# setup.net
KiCad netlist of a schematic drawn in EAGLE
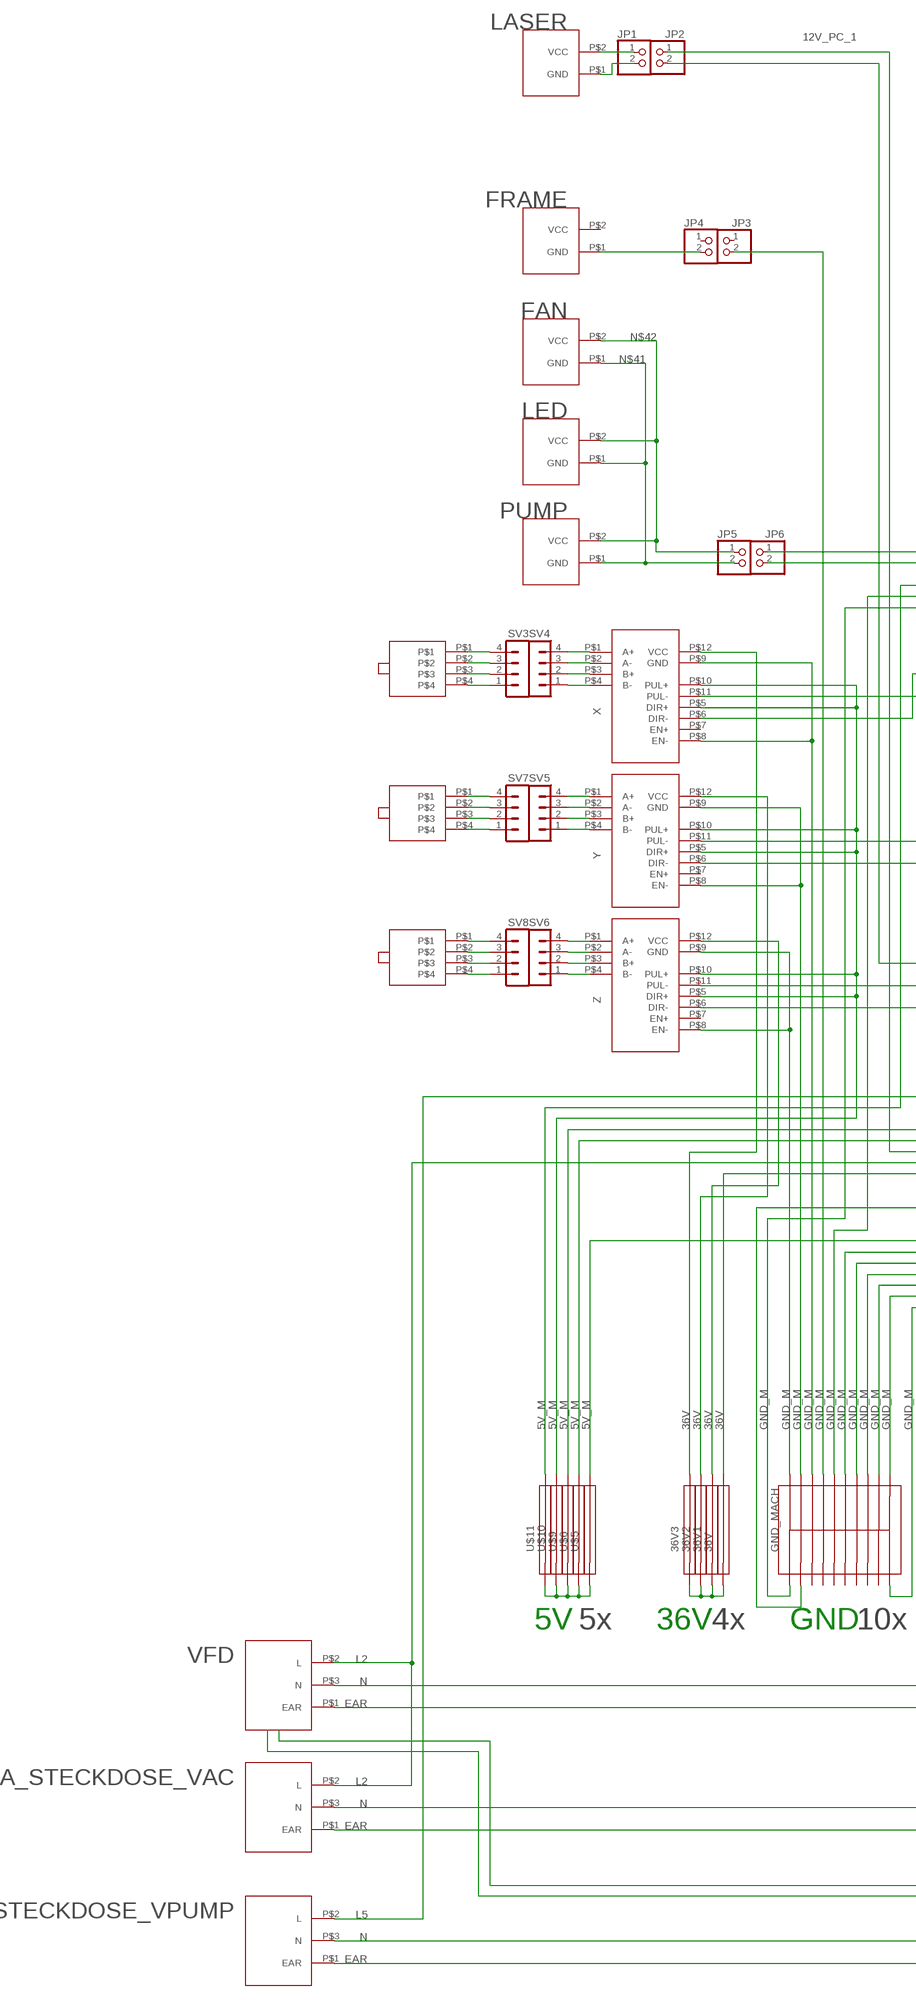
[diagram p0: schematic, sheet 1, part 1 of 3]
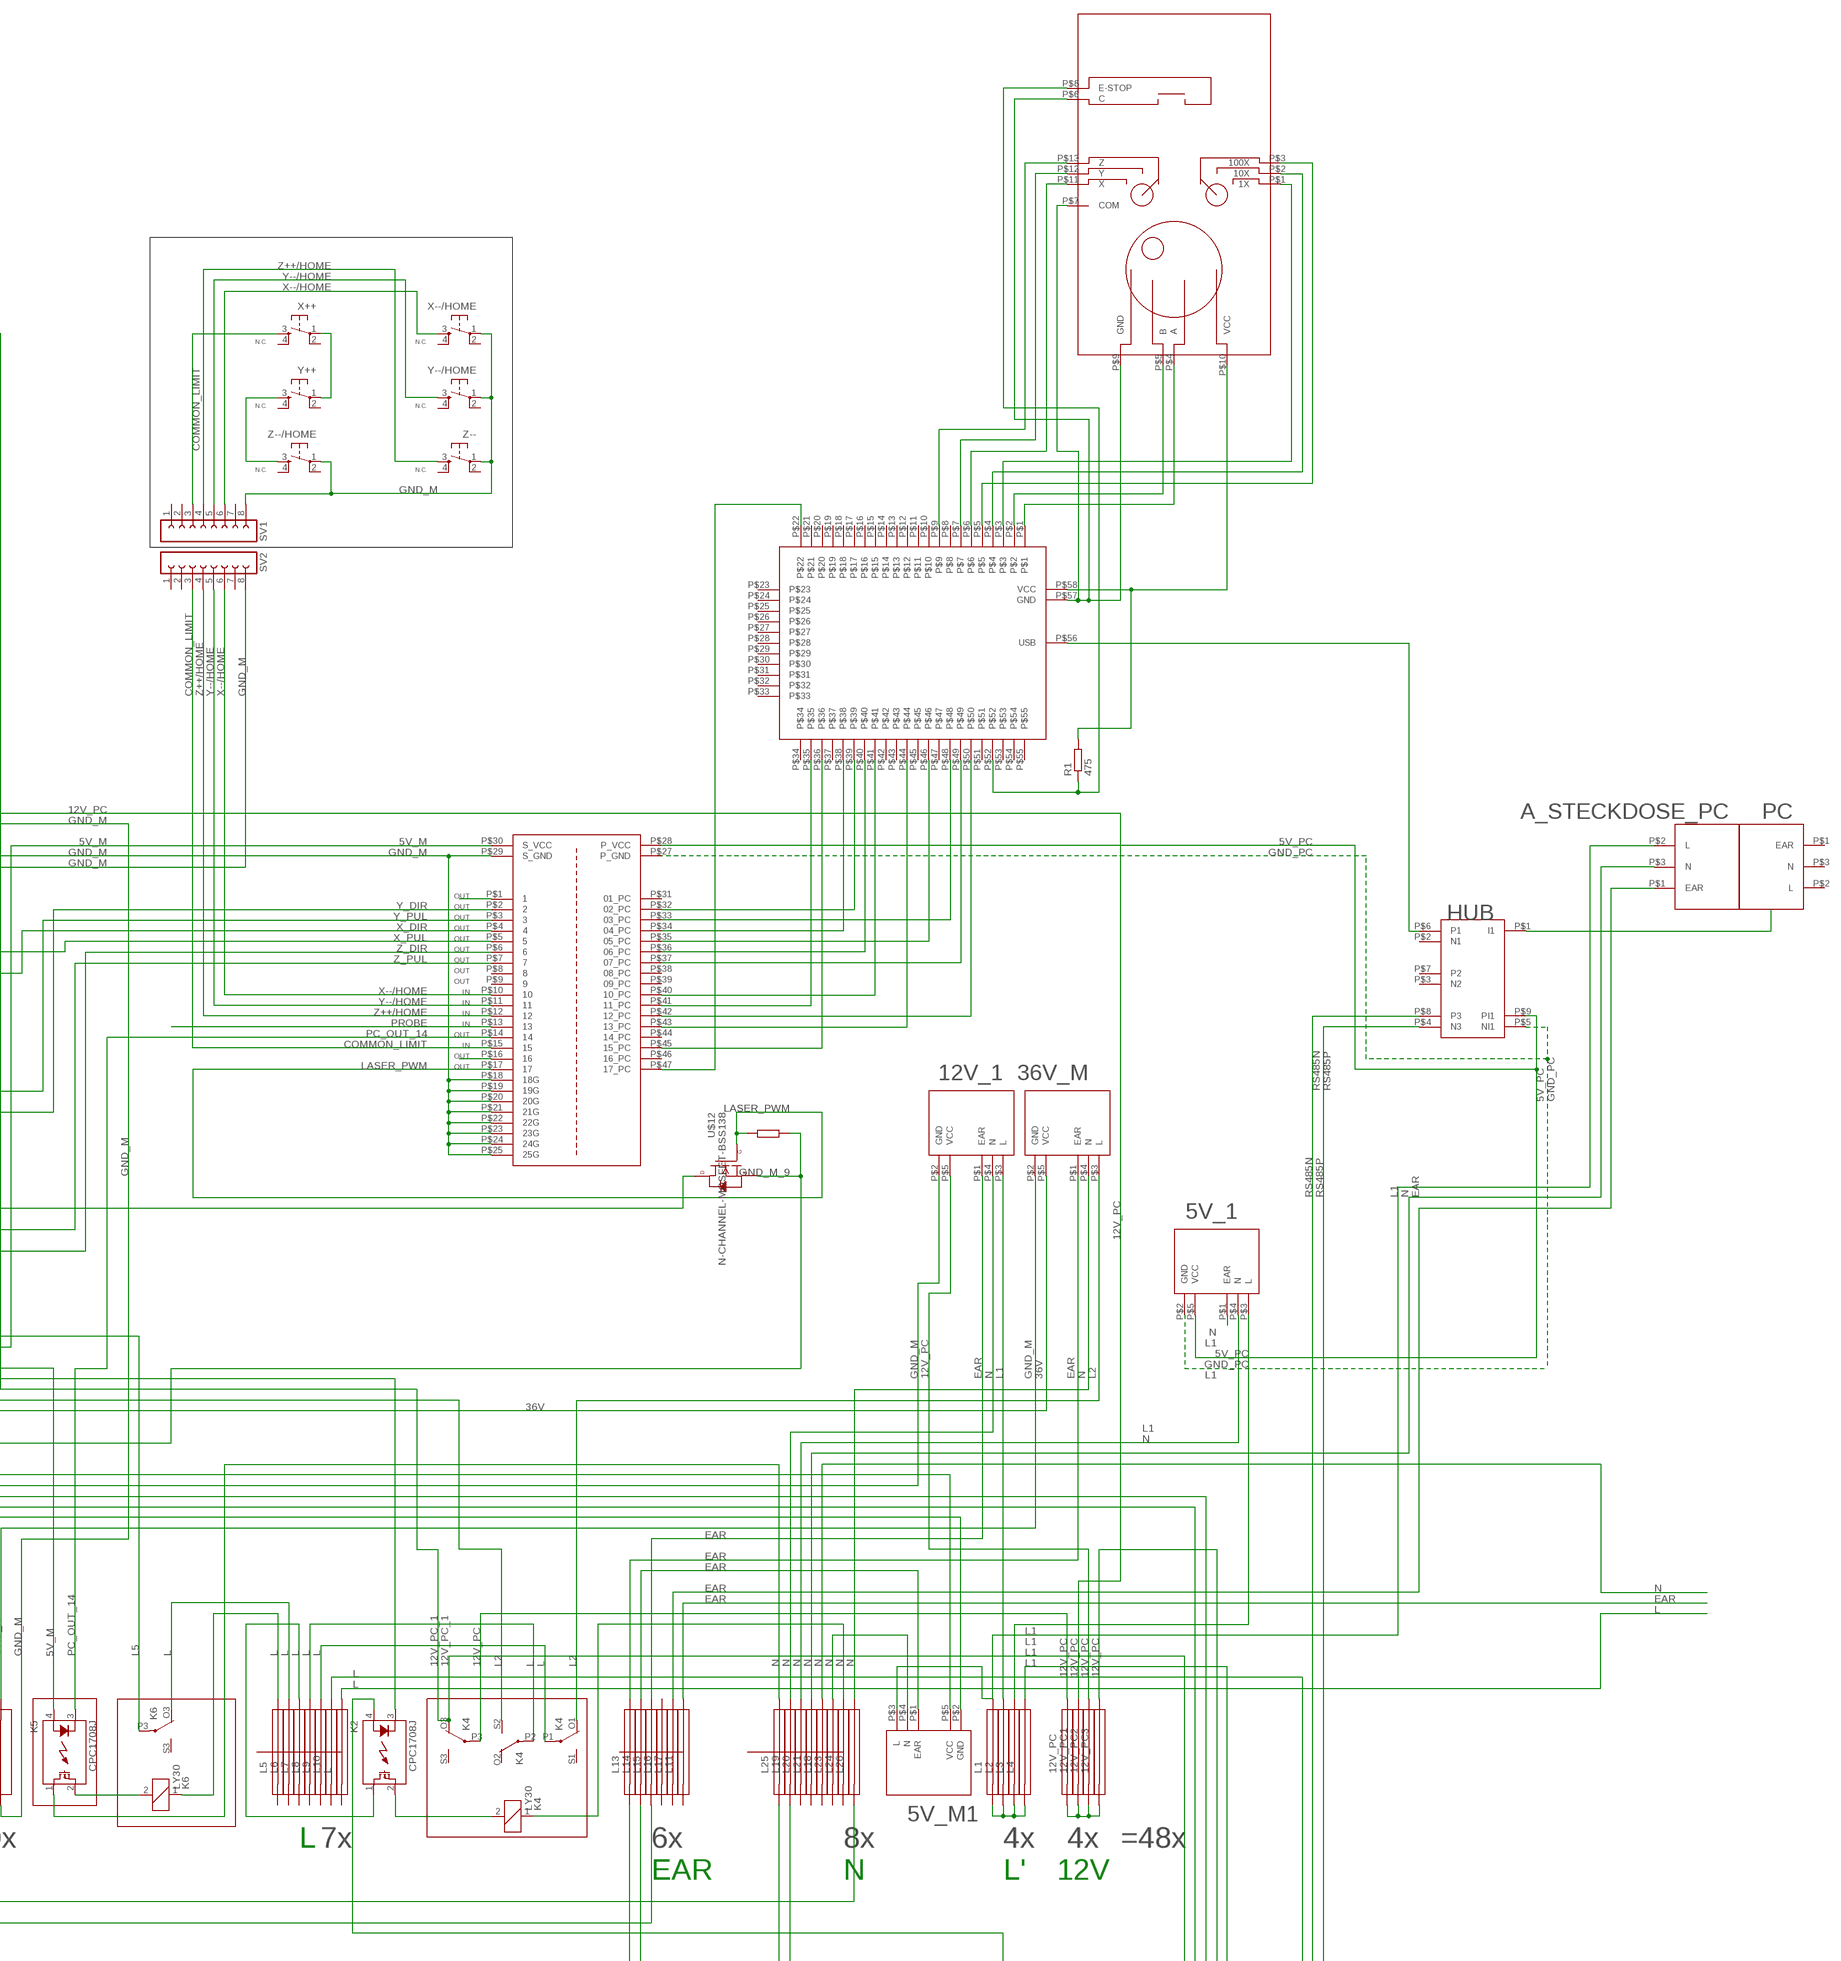
[diagram p1: schematic, sheet 1, part 2 of 3]
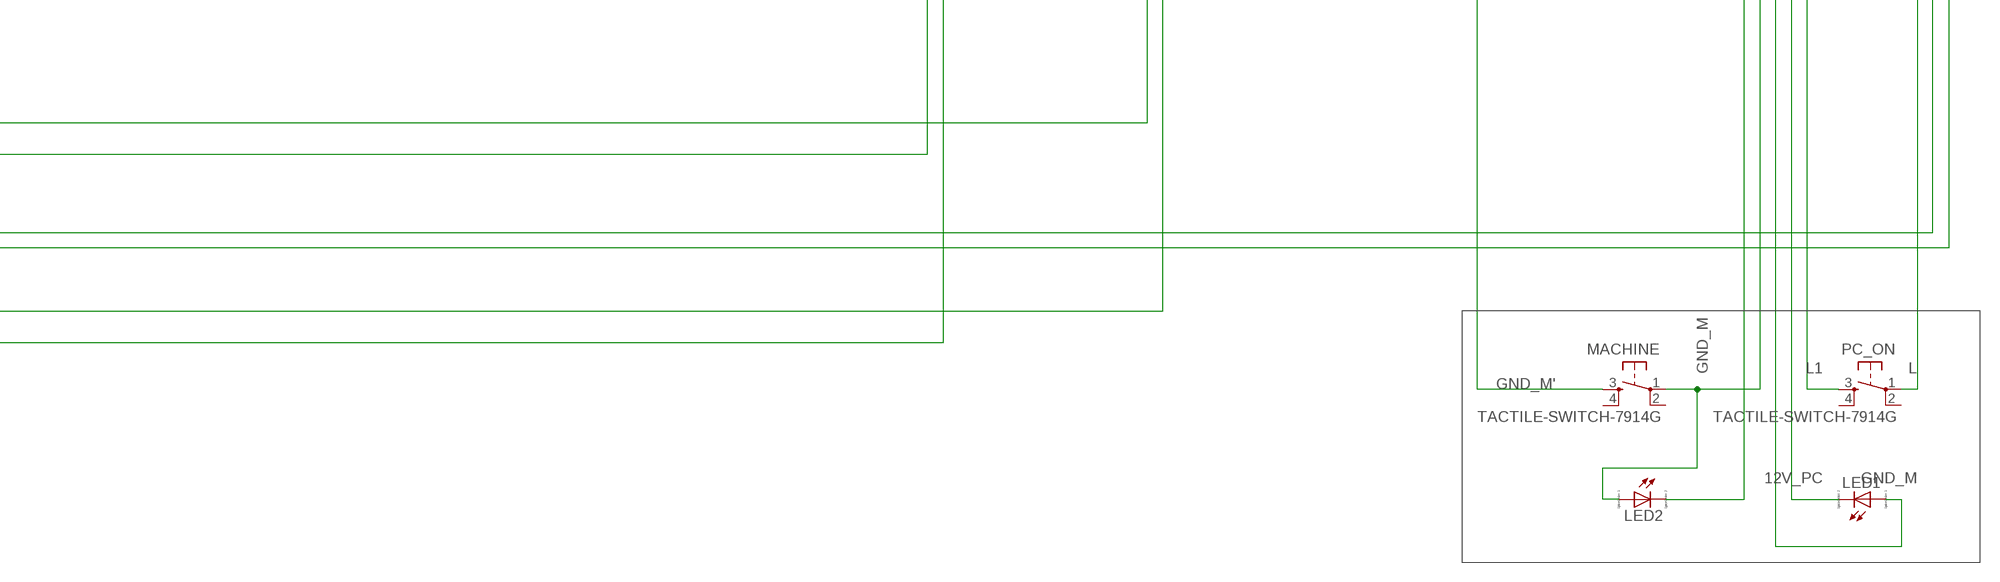
[diagram p2: schematic, sheet 1, part 3 of 3]

(export (version "E")
  (design (tool "Eeschema 10.0.6"))
  (components
    (comp (ref "5V_1")
      (value "PWR")
      (footprint "eagle-import:PWR")
      (libsource (lib "eagle-import") (part "PWR"))
    )
    (comp (ref "5V_M1")
      (value "PWR")
      (footprint "eagle-import:PWR")
      (libsource (lib "eagle-import") (part "PWR"))
    )
    (comp (ref "12V_1")
      (value "PWR")
      (footprint "eagle-import:PWR")
      (libsource (lib "eagle-import") (part "PWR"))
    )
    (comp (ref "12V_PC")
      (value "SINGLE_CONNECTOR")
      (footprint "eagle-import:CONNECTOR")
      (libsource (lib "eagle-import") (part "SINGLE_CONNECTOR"))
    )
    (comp (ref "12V_PC1")
      (value "SINGLE_CONNECTOR")
      (footprint "eagle-import:CONNECTOR")
      (libsource (lib "eagle-import") (part "SINGLE_CONNECTOR"))
    )
    (comp (ref "12V_PC2")
      (value "SINGLE_CONNECTOR")
      (footprint "eagle-import:CONNECTOR")
      (libsource (lib "eagle-import") (part "SINGLE_CONNECTOR"))
    )
    (comp (ref "12V_PC3")
      (value "SINGLE_CONNECTOR")
      (footprint "eagle-import:CONNECTOR")
      (libsource (lib "eagle-import") (part "SINGLE_CONNECTOR"))
    )
    (comp (ref "36V")
      (value "SINGLE_CONNECTOR")
      (footprint "eagle-import:CONNECTOR")
      (libsource (lib "eagle-import") (part "SINGLE_CONNECTOR"))
    )
    (comp (ref "36V1")
      (value "SINGLE_CONNECTOR")
      (footprint "eagle-import:CONNECTOR")
      (libsource (lib "eagle-import") (part "SINGLE_CONNECTOR"))
    )
    (comp (ref "36V2")
      (value "SINGLE_CONNECTOR")
      (footprint "eagle-import:CONNECTOR")
      (libsource (lib "eagle-import") (part "SINGLE_CONNECTOR"))
    )
    (comp (ref "36V3")
      (value "SINGLE_CONNECTOR")
      (footprint "eagle-import:CONNECTOR")
      (libsource (lib "eagle-import") (part "SINGLE_CONNECTOR"))
    )
    (comp (ref "36V_M")
      (value "PWR")
      (footprint "eagle-import:PWR")
      (libsource (lib "eagle-import") (part "PWR"))
    )
    (comp (ref "A_STECKDOSE_PC")
      (value "230VDEV")
      (footprint "eagle-import:230V")
      (libsource (lib "eagle-import") (part "230VDEV"))
    )
    (comp (ref "A_STECKDOSE_VAC")
      (value "230VDEV")
      (footprint "eagle-import:230V")
      (libsource (lib "eagle-import") (part "230VDEV"))
    )
    (comp (ref "A_STECKDOSE_VPUMP")
      (value "230VDEV")
      (footprint "eagle-import:230V")
      (libsource (lib "eagle-import") (part "230VDEV"))
    )
    (comp (ref "FAN")
      (value "LV_DEV")
      (footprint "eagle-import:PUMP")
      (libsource (lib "eagle-import") (part "LV_DEV"))
    )
    (comp (ref "FRAME")
      (value "LV_DEV")
      (footprint "eagle-import:PUMP")
      (libsource (lib "eagle-import") (part "LV_DEV"))
    )
    (comp (ref "GND_MACH")
      (value "CONNECTOR")
      (footprint "eagle-import:CONNECTOR")
      (libsource (lib "eagle-import") (part "CONNECTOR"))
    )
    (comp (ref "JP1")
      (value "PINHD-1X2")
      (footprint "eagle-import:1X02")
      (libsource (lib "eagle-import") (part "PINHD-1X2"))
    )
    (comp (ref "JP2")
      (value "PINHD-1X2")
      (footprint "eagle-import:1X02")
      (libsource (lib "eagle-import") (part "PINHD-1X2"))
    )
    (comp (ref "JP3")
      (value "PINHD-1X2")
      (footprint "eagle-import:1X02")
      (libsource (lib "eagle-import") (part "PINHD-1X2"))
    )
    (comp (ref "JP4")
      (value "PINHD-1X2")
      (footprint "eagle-import:1X02")
      (libsource (lib "eagle-import") (part "PINHD-1X2"))
    )
    (comp (ref "JP5")
      (value "PINHD-1X2")
      (footprint "eagle-import:1X02")
      (libsource (lib "eagle-import") (part "PINHD-1X2"))
    )
    (comp (ref "JP6")
      (value "PINHD-1X2")
      (footprint "eagle-import:1X02")
      (libsource (lib "eagle-import") (part "PINHD-1X2"))
    )
    (comp (ref "K2")
      (value "CPC1708J")
      (footprint "eagle-import:I4-PAC")
      (libsource (lib "eagle-import") (part "CPC1708J"))
    )
    (comp (ref "K4")
      (value "LY30")
      (footprint "eagle-import:LY30")
      (libsource (lib "eagle-import") (part "LY30"))
    )
    (comp (ref "K5")
      (value "CPC1708J")
      (footprint "eagle-import:I4-PAC")
      (libsource (lib "eagle-import") (part "CPC1708J"))
    )
    (comp (ref "K6")
      (value "LY30")
      (footprint "eagle-import:LY30")
      (libsource (lib "eagle-import") (part "LY30"))
    )
    (comp (ref "L")
      (value "SINGLE_CONNECTOR")
      (footprint "eagle-import:CONNECTOR")
      (libsource (lib "eagle-import") (part "SINGLE_CONNECTOR"))
    )
    (comp (ref "L1")
      (value "SINGLE_CONNECTOR")
      (footprint "eagle-import:CONNECTOR")
      (libsource (lib "eagle-import") (part "SINGLE_CONNECTOR"))
    )
    (comp (ref "L2")
      (value "SINGLE_CONNECTOR")
      (footprint "eagle-import:CONNECTOR")
      (libsource (lib "eagle-import") (part "SINGLE_CONNECTOR"))
    )
    (comp (ref "L3")
      (value "SINGLE_CONNECTOR")
      (footprint "eagle-import:CONNECTOR")
      (libsource (lib "eagle-import") (part "SINGLE_CONNECTOR"))
    )
    (comp (ref "L4")
      (value "SINGLE_CONNECTOR")
      (footprint "eagle-import:CONNECTOR")
      (libsource (lib "eagle-import") (part "SINGLE_CONNECTOR"))
    )
    (comp (ref "L5")
      (value "SINGLE_CONNECTOR")
      (footprint "eagle-import:CONNECTOR")
      (libsource (lib "eagle-import") (part "SINGLE_CONNECTOR"))
    )
    (comp (ref "L6")
      (value "SINGLE_CONNECTOR")
      (footprint "eagle-import:CONNECTOR")
      (libsource (lib "eagle-import") (part "SINGLE_CONNECTOR"))
    )
    (comp (ref "L7")
      (value "SINGLE_CONNECTOR")
      (footprint "eagle-import:CONNECTOR")
      (libsource (lib "eagle-import") (part "SINGLE_CONNECTOR"))
    )
    (comp (ref "L8")
      (value "SINGLE_CONNECTOR")
      (footprint "eagle-import:CONNECTOR")
      (libsource (lib "eagle-import") (part "SINGLE_CONNECTOR"))
    )
    (comp (ref "L9")
      (value "SINGLE_CONNECTOR")
      (footprint "eagle-import:CONNECTOR")
      (libsource (lib "eagle-import") (part "SINGLE_CONNECTOR"))
    )
    (comp (ref "L10")
      (value "SINGLE_CONNECTOR")
      (footprint "eagle-import:CONNECTOR")
      (libsource (lib "eagle-import") (part "SINGLE_CONNECTOR"))
    )
    (comp (ref "L11")
      (value "SINGLE_CONNECTOR")
      (footprint "eagle-import:CONNECTOR")
      (libsource (lib "eagle-import") (part "SINGLE_CONNECTOR"))
    )
    (comp (ref "L13")
      (value "SINGLE_CONNECTOR")
      (footprint "eagle-import:CONNECTOR")
      (libsource (lib "eagle-import") (part "SINGLE_CONNECTOR"))
    )
    (comp (ref "L14")
      (value "SINGLE_CONNECTOR")
      (footprint "eagle-import:CONNECTOR")
      (libsource (lib "eagle-import") (part "SINGLE_CONNECTOR"))
    )
    (comp (ref "L15")
      (value "SINGLE_CONNECTOR")
      (footprint "eagle-import:CONNECTOR")
      (libsource (lib "eagle-import") (part "SINGLE_CONNECTOR"))
    )
    (comp (ref "L16")
      (value "SINGLE_CONNECTOR")
      (footprint "eagle-import:CONNECTOR")
      (libsource (lib "eagle-import") (part "SINGLE_CONNECTOR"))
    )
    (comp (ref "L17")
      (value "SINGLE_CONNECTOR")
      (footprint "eagle-import:CONNECTOR")
      (libsource (lib "eagle-import") (part "SINGLE_CONNECTOR"))
    )
    (comp (ref "L18")
      (value "SINGLE_CONNECTOR")
      (footprint "eagle-import:CONNECTOR")
      (libsource (lib "eagle-import") (part "SINGLE_CONNECTOR"))
    )
    (comp (ref "L19")
      (value "SINGLE_CONNECTOR")
      (footprint "eagle-import:CONNECTOR")
      (libsource (lib "eagle-import") (part "SINGLE_CONNECTOR"))
    )
    (comp (ref "L20")
      (value "SINGLE_CONNECTOR")
      (footprint "eagle-import:CONNECTOR")
      (libsource (lib "eagle-import") (part "SINGLE_CONNECTOR"))
    )
    (comp (ref "L21")
      (value "SINGLE_CONNECTOR")
      (footprint "eagle-import:CONNECTOR")
      (libsource (lib "eagle-import") (part "SINGLE_CONNECTOR"))
    )
    (comp (ref "L23")
      (value "SINGLE_CONNECTOR")
      (footprint "eagle-import:CONNECTOR")
      (libsource (lib "eagle-import") (part "SINGLE_CONNECTOR"))
    )
    (comp (ref "L24")
      (value "SINGLE_CONNECTOR")
      (footprint "eagle-import:CONNECTOR")
      (libsource (lib "eagle-import") (part "SINGLE_CONNECTOR"))
    )
    (comp (ref "L25")
      (value "SINGLE_CONNECTOR")
      (footprint "eagle-import:CONNECTOR")
      (libsource (lib "eagle-import") (part "SINGLE_CONNECTOR"))
    )
    (comp (ref "L26")
      (value "SINGLE_CONNECTOR")
      (footprint "eagle-import:CONNECTOR")
      (libsource (lib "eagle-import") (part "SINGLE_CONNECTOR"))
    )
    (comp (ref "LASER")
      (value "LV_DEV")
      (footprint "eagle-import:PUMP")
      (libsource (lib "eagle-import") (part "LV_DEV"))
    )
    (comp (ref "LED")
      (value "LV_DEV")
      (footprint "eagle-import:PUMP")
      (libsource (lib "eagle-import") (part "LV_DEV"))
    )
    (comp (ref "LED1")
      (value "LED_E")
      (footprint "eagle-import:LED_1206")
      (libsource (lib "eagle-import") (part "LED_E"))
    )
    (comp (ref "LED2")
      (value "LED_E")
      (footprint "eagle-import:LED_1206")
      (libsource (lib "eagle-import") (part "LED_E"))
    )
    (comp (ref "MACHINE")
      (value "TACTILE-SWITCH-7914G")
      (footprint "eagle-import:7914G")
      (libsource (lib "eagle-import") (part "TACTILE-SWITCH-7914G"))
    )
    (comp (ref "PC")
      (value "230VDEV")
      (footprint "eagle-import:230V")
      (libsource (lib "eagle-import") (part "230VDEV"))
    )
    (comp (ref "PC_ON")
      (value "TACTILE-SWITCH-7914G")
      (footprint "eagle-import:7914G")
      (libsource (lib "eagle-import") (part "TACTILE-SWITCH-7914G"))
    )
    (comp (ref "PUMP")
      (value "LV_DEV")
      (footprint "eagle-import:PUMP")
      (libsource (lib "eagle-import") (part "LV_DEV"))
    )
    (comp (ref "R1")
      (value "475")
      (footprint "eagle-import:0204V")
      (libsource (lib "eagle-import") (part "R-EU_0204/2V"))
    )
    (comp (ref "SV1")
      (value "FE08-1")
      (footprint "eagle-import:FE08")
      (libsource (lib "eagle-import") (part "FE08-1"))
    )
    (comp (ref "SV2")
      (value "FE08-1")
      (footprint "eagle-import:FE08")
      (libsource (lib "eagle-import") (part "FE08-1"))
    )
    (comp (ref "SV3")
      (value "MA04-1")
      (footprint "eagle-import:MA04-1")
      (libsource (lib "eagle-import") (part "MA04-1"))
    )
    (comp (ref "SV4")
      (value "MA04-1")
      (footprint "eagle-import:MA04-1")
      (libsource (lib "eagle-import") (part "MA04-1"))
    )
    (comp (ref "SV5")
      (value "MA04-1")
      (footprint "eagle-import:MA04-1")
      (libsource (lib "eagle-import") (part "MA04-1"))
    )
    (comp (ref "SV6")
      (value "MA04-1")
      (footprint "eagle-import:MA04-1")
      (libsource (lib "eagle-import") (part "MA04-1"))
    )
    (comp (ref "SV7")
      (value "MA04-1")
      (footprint "eagle-import:MA04-1")
      (libsource (lib "eagle-import") (part "MA04-1"))
    )
    (comp (ref "SV8")
      (value "MA04-1")
      (footprint "eagle-import:MA04-1")
      (libsource (lib "eagle-import") (part "MA04-1"))
    )
    (comp (ref "U$1")
      (value "BOB")
      (footprint "eagle-import:BOB")
      (libsource (lib "eagle-import") (part "BOB"))
    )
    (comp (ref "U$2")
      (value "HUB")
      (footprint "eagle-import:HUB")
      (libsource (lib "eagle-import") (part "HUB"))
    )
    (comp (ref "U$3")
      (value "MOTOR")
      (footprint "eagle-import:MOTOR")
      (libsource (lib "eagle-import") (part "MOTOR"))
    )
    (comp (ref "U$4")
      (value "POKEY57U")
      (footprint "eagle-import:POKEY57U")
      (libsource (lib "eagle-import") (part "POKEY57U"))
    )
    (comp (ref "U$5")
      (value "SINGLE_CONNECTOR")
      (footprint "eagle-import:CONNECTOR")
      (libsource (lib "eagle-import") (part "SINGLE_CONNECTOR"))
    )
    (comp (ref "U$6")
      (value "SINGLE_CONNECTOR")
      (footprint "eagle-import:CONNECTOR")
      (libsource (lib "eagle-import") (part "SINGLE_CONNECTOR"))
    )
    (comp (ref "U$7")
      (value "MOTOR")
      (footprint "eagle-import:MOTOR")
      (libsource (lib "eagle-import") (part "MOTOR"))
    )
    (comp (ref "U$8")
      (value "MOTOR")
      (footprint "eagle-import:MOTOR")
      (libsource (lib "eagle-import") (part "MOTOR"))
    )
    (comp (ref "U$9")
      (value "SINGLE_CONNECTOR")
      (footprint "eagle-import:CONNECTOR")
      (libsource (lib "eagle-import") (part "SINGLE_CONNECTOR"))
    )
    (comp (ref "U$10")
      (value "SINGLE_CONNECTOR")
      (footprint "eagle-import:CONNECTOR")
      (libsource (lib "eagle-import") (part "SINGLE_CONNECTOR"))
    )
    (comp (ref "U$11")
      (value "SINGLE_CONNECTOR")
      (footprint "eagle-import:CONNECTOR")
      (libsource (lib "eagle-import") (part "SINGLE_CONNECTOR"))
    )
    (comp (ref "U$12")
      (value "N-CHANNEL-MOSFET-BSS138")
      (footprint "eagle-import:SOT23-3")
      (libsource (lib "eagle-import") (part "N-CHANNEL-MOSFET-BSS138"))
    )
    (comp (ref "U$13")
      (value "PENDANT")
      (footprint "eagle-import:PENDANT")
      (libsource (lib "eagle-import") (part "PENDANT"))
    )
    (comp (ref "VFD")
      (value "230VDEV")
      (footprint "eagle-import:230V")
      (libsource (lib "eagle-import") (part "230VDEV"))
    )
    (comp (ref "X")
      (value "DRIVER")
      (footprint "eagle-import:DRIVER")
      (libsource (lib "eagle-import") (part "DRIVER"))
    )
    (comp (ref "X++")
      (value "TACTILE-SWITCH-7914G")
      (footprint "eagle-import:7914G")
      (libsource (lib "eagle-import") (part "TACTILE-SWITCH-7914G"))
    )
    (comp (ref "X--/HOME")
      (value "TACTILE-SWITCH-7914G")
      (footprint "eagle-import:7914G")
      (libsource (lib "eagle-import") (part "TACTILE-SWITCH-7914G"))
    )
    (comp (ref "Y")
      (value "DRIVER")
      (footprint "eagle-import:DRIVER")
      (libsource (lib "eagle-import") (part "DRIVER"))
    )
    (comp (ref "Y++")
      (value "TACTILE-SWITCH-7914G")
      (footprint "eagle-import:7914G")
      (libsource (lib "eagle-import") (part "TACTILE-SWITCH-7914G"))
    )
    (comp (ref "Y--/HOME")
      (value "TACTILE-SWITCH-7914G")
      (footprint "eagle-import:7914G")
      (libsource (lib "eagle-import") (part "TACTILE-SWITCH-7914G"))
    )
    (comp (ref "Z")
      (value "DRIVER")
      (footprint "eagle-import:DRIVER")
      (libsource (lib "eagle-import") (part "DRIVER"))
    )
    (comp (ref "Z--")
      (value "TACTILE-SWITCH-7914G")
      (footprint "eagle-import:7914G")
      (libsource (lib "eagle-import") (part "TACTILE-SWITCH-7914G"))
    )
    (comp (ref "Z--/HOME")
      (value "TACTILE-SWITCH-7914G")
      (footprint "eagle-import:7914G")
      (libsource (lib "eagle-import") (part "TACTILE-SWITCH-7914G"))
    )
  )
  (nets
    (net (code "1") (name "/5V_M") (class "Default")
      (node (ref "5V_M1") (pin "P$5") (pinfunction "VCC_P$5") (pintype "bidirectional"))
      (node (ref "K2") (pin "3") (pinfunction "K_3") (pintype "passive"))
      (node (ref "K5") (pin "4") (pinfunction "A_4") (pintype "passive"))
      (node (ref "U$1") (pin "P$30") (pinfunction "S_VCC_P$30") (pintype "bidirectional"))
      (node (ref "U$10") (pin "P$2") (pinfunction "P$11_P$2") (pintype "bidirectional"))
      (node (ref "U$11") (pin "P$2") (pinfunction "P$11_P$2") (pintype "bidirectional"))
      (node (ref "U$5") (pin "P$2") (pinfunction "P$11_P$2") (pintype "bidirectional"))
      (node (ref "U$6") (pin "P$2") (pinfunction "P$11_P$2") (pintype "bidirectional"))
      (node (ref "U$9") (pin "P$2") (pinfunction "P$11_P$2") (pintype "bidirectional"))
      (node (ref "X") (pin "P$10") (pinfunction "PUL+_P$10") (pintype "bidirectional"))
      (node (ref "X") (pin "P$5") (pinfunction "DIR+_P$5") (pintype "bidirectional"))
      (node (ref "Y") (pin "P$10") (pinfunction "PUL+_P$10") (pintype "bidirectional"))
      (node (ref "Y") (pin "P$5") (pinfunction "DIR+_P$5") (pintype "bidirectional"))
      (node (ref "Z") (pin "P$10") (pinfunction "PUL+_P$10") (pintype "bidirectional"))
      (node (ref "Z") (pin "P$5") (pinfunction "DIR+_P$5") (pintype "bidirectional"))
    )
    (net (code "2") (name "/5V_PC") (class "Default")
      (node (ref "5V_1") (pin "P$5") (pinfunction "VCC_P$5") (pintype "bidirectional"))
      (node (ref "U$1") (pin "P$28") (pinfunction "P_VCC_P$28") (pintype "bidirectional"))
      (node (ref "U$2") (pin "P$6") (pinfunction "P1_P$6") (pintype "bidirectional"))
      (node (ref "U$2") (pin "P$9") (pinfunction "PI1_P$9") (pintype "bidirectional"))
      (node (ref "U$4") (pin "P$56") (pinfunction "USB_P$56") (pintype "bidirectional"))
    )
    (net (code "3") (name "/12V_PC") (class "Default")
      (node (ref "12V_1") (pin "P$5") (pinfunction "VCC_P$5") (pintype "bidirectional"))
      (node (ref "12V_PC") (pin "P$2") (pinfunction "P$11_P$2") (pintype "bidirectional"))
      (node (ref "12V_PC1") (pin "P$2") (pinfunction "P$11_P$2") (pintype "bidirectional"))
      (node (ref "12V_PC2") (pin "P$2") (pinfunction "P$11_P$2") (pintype "bidirectional"))
      (node (ref "12V_PC3") (pin "P$2") (pinfunction "P$11_P$2") (pintype "bidirectional"))
      (node (ref "JP6") (pin "1") (pinfunction "1_1") (pintype "passive"))
      (node (ref "K4") (pin "P3") (pinfunction "P_P3") (pintype "passive"))
      (node (ref "LED1") (pin "C") (pinfunction "C_C") (pintype "passive"))
    )
    (net (code "4") (name "/12V_PC_1") (class "Default")
      (node (ref "JP2") (pin "1") (pinfunction "1_1") (pintype "passive"))
      (node (ref "K4") (pin "O3") (pinfunction "O_O3") (pintype "passive"))
      (node (ref "LED2") (pin "C") (pinfunction "C_C") (pintype "passive"))
    )
    (net (code "5") (name "/36V") (class "Default")
      (node (ref "36V") (pin "P$2") (pinfunction "P$11_P$2") (pintype "bidirectional"))
      (node (ref "36V1") (pin "P$2") (pinfunction "P$11_P$2") (pintype "bidirectional"))
      (node (ref "36V2") (pin "P$2") (pinfunction "P$11_P$2") (pintype "bidirectional"))
      (node (ref "36V3") (pin "P$2") (pinfunction "P$11_P$2") (pintype "bidirectional"))
      (node (ref "36V_M") (pin "P$5") (pinfunction "VCC_P$5") (pintype "bidirectional"))
      (node (ref "X") (pin "P$12") (pinfunction "VCC_P$12") (pintype "bidirectional"))
      (node (ref "Y") (pin "P$12") (pinfunction "VCC_P$12") (pintype "bidirectional"))
      (node (ref "Z") (pin "P$12") (pinfunction "VCC_P$12") (pintype "bidirectional"))
    )
    (net (code "6") (name "/COMMON_LIMIT") (class "Default")
      (node (ref "SV1") (pin "3") (pinfunction "3_3") (pintype "passive"))
      (node (ref "SV2") (pin "3") (pinfunction "3_3") (pintype "passive"))
      (node (ref "U$1") (pin "P$15") (pinfunction "15_P$15") (pintype "bidirectional"))
      (node (ref "X++") (pin "3") (pinfunction "3_3") (pintype "passive"))
    )
    (net (code "7") (name "/EAR") (class "Default")
      (node (ref "12V_1") (pin "P$1") (pinfunction "EAR_P$1") (pintype "bidirectional"))
      (node (ref "36V_M") (pin "P$1") (pinfunction "EAR_P$1") (pintype "bidirectional"))
      (node (ref "5V_M1") (pin "P$1") (pinfunction "EAR_P$1") (pintype "bidirectional"))
      (node (ref "A_STECKDOSE_PC") (pin "P$1") (pinfunction "EAR_P$1") (pintype "bidirectional"))
      (node (ref "A_STECKDOSE_VAC") (pin "P$1") (pinfunction "EAR_P$1") (pintype "bidirectional"))
      (node (ref "A_STECKDOSE_VPUMP") (pin "P$1") (pinfunction "EAR_P$1") (pintype "bidirectional"))
      (node (ref "L11") (pin "P$2") (pinfunction "P$11_P$2") (pintype "bidirectional"))
      (node (ref "L13") (pin "P$1") (pinfunction "P$1_P$1") (pintype "bidirectional"))
      (node (ref "L13") (pin "P$2") (pinfunction "P$11_P$2") (pintype "bidirectional"))
      (node (ref "L14") (pin "P$1") (pinfunction "P$1_P$1") (pintype "bidirectional"))
      (node (ref "L14") (pin "P$2") (pinfunction "P$11_P$2") (pintype "bidirectional"))
      (node (ref "L15") (pin "P$1") (pinfunction "P$1_P$1") (pintype "bidirectional"))
      (node (ref "L15") (pin "P$2") (pinfunction "P$11_P$2") (pintype "bidirectional"))
      (node (ref "L17") (pin "P$2") (pinfunction "P$11_P$2") (pintype "bidirectional"))
      (node (ref "VFD") (pin "P$1") (pinfunction "EAR_P$1") (pintype "bidirectional"))
    )
    (net (code "8") (name "/GND_M") (class "Default")
      (node (ref "12V_1") (pin "P$2") (pinfunction "GND_P$2") (pintype "bidirectional"))
      (node (ref "36V_M") (pin "P$2") (pinfunction "GND_P$2") (pintype "bidirectional"))
      (node (ref "5V_M1") (pin "P$2") (pinfunction "GND_P$2") (pintype "bidirectional"))
      (node (ref "GND_MACH") (pin "P$1") (pinfunction "P$1_P$1") (pintype "bidirectional"))
      (node (ref "GND_MACH") (pin "P$10") (pinfunction "P$10_P$10") (pintype "bidirectional"))
      (node (ref "GND_MACH") (pin "P$11") (pinfunction "P$11_P$11") (pintype "bidirectional"))
      (node (ref "GND_MACH") (pin "P$12") (pinfunction "P$12_P$12") (pintype "bidirectional"))
      (node (ref "GND_MACH") (pin "P$13") (pinfunction "P$13_P$13") (pintype "bidirectional"))
      (node (ref "GND_MACH") (pin "P$14") (pinfunction "P$14_P$14") (pintype "bidirectional"))
      (node (ref "GND_MACH") (pin "P$15") (pinfunction "P$15_P$15") (pintype "bidirectional"))
      (node (ref "GND_MACH") (pin "P$16") (pinfunction "P$16_P$16") (pintype "bidirectional"))
      (node (ref "GND_MACH") (pin "P$17") (pinfunction "P$17_P$17") (pintype "bidirectional"))
      (node (ref "GND_MACH") (pin "P$18") (pinfunction "P$18_P$18") (pintype "bidirectional"))
      (node (ref "GND_MACH") (pin "P$19") (pinfunction "P$19_P$19") (pintype "bidirectional"))
      (node (ref "GND_MACH") (pin "P$20") (pinfunction "P$20_P$20") (pintype "bidirectional"))
      (node (ref "JP3") (pin "2") (pinfunction "2_2") (pintype "passive"))
      (node (ref "JP6") (pin "2") (pinfunction "2_2") (pintype "passive"))
      (node (ref "LED1") (pin "A") (pinfunction "A_A") (pintype "passive"))
      (node (ref "LED2") (pin "A") (pinfunction "A_A") (pintype "passive"))
      (node (ref "MACHINE") (pin "1") (pinfunction "1_1") (pintype "passive"))
      (node (ref "SV1") (pin "8") (pinfunction "8_8") (pintype "passive"))
      (node (ref "SV2") (pin "8") (pinfunction "8_8") (pintype "passive"))
      (node (ref "U$1") (pin "P$18") (pinfunction "18G_P$18") (pintype "bidirectional"))
      (node (ref "U$1") (pin "P$19") (pinfunction "19G_P$19") (pintype "bidirectional"))
      (node (ref "U$1") (pin "P$20") (pinfunction "20G_P$20") (pintype "bidirectional"))
      (node (ref "U$1") (pin "P$21") (pinfunction "21G_P$21") (pintype "bidirectional"))
      (node (ref "U$1") (pin "P$22") (pinfunction "22G_P$22") (pintype "bidirectional"))
      (node (ref "U$1") (pin "P$23") (pinfunction "23G_P$23") (pintype "bidirectional"))
      (node (ref "U$1") (pin "P$24") (pinfunction "24G_P$24") (pintype "bidirectional"))
      (node (ref "U$1") (pin "P$25") (pinfunction "25G_P$25") (pintype "bidirectional"))
      (node (ref "U$1") (pin "P$29") (pinfunction "S_GND_P$29") (pintype "bidirectional"))
      (node (ref "X") (pin "P$8") (pinfunction "EN-_P$8") (pintype "bidirectional"))
      (node (ref "X") (pin "P$9") (pinfunction "GND_P$9") (pintype "bidirectional"))
      (node (ref "X--/HOME") (pin "1") (pinfunction "1_1") (pintype "passive"))
      (node (ref "Y") (pin "P$8") (pinfunction "EN-_P$8") (pintype "bidirectional"))
      (node (ref "Y") (pin "P$9") (pinfunction "GND_P$9") (pintype "bidirectional"))
      (node (ref "Y--/HOME") (pin "1") (pinfunction "1_1") (pintype "passive"))
      (node (ref "Z") (pin "P$8") (pinfunction "EN-_P$8") (pintype "bidirectional"))
      (node (ref "Z") (pin "P$9") (pinfunction "GND_P$9") (pintype "bidirectional"))
      (node (ref "Z--") (pin "1") (pinfunction "1_1") (pintype "passive"))
      (node (ref "Z--/HOME") (pin "1") (pinfunction "1_1") (pintype "passive"))
    )
    (net (code "9") (name "/GND_M'") (class "Default")
      (node (ref "K2") (pin "4") (pinfunction "A_4") (pintype "passive"))
      (node (ref "MACHINE") (pin "3") (pinfunction "3_3") (pintype "passive"))
    )
    (net (code "10") (name "/GND_M_9") (class "Default")
      (node (ref "GND_MACH") (pin "P$2") (pinfunction "P$2_P$2") (pintype "bidirectional"))
      (node (ref "U$12") (pin "2") (pinfunction "S_2") (pintype "passive"))
    )
    (net (code "11") (name "/GND_PC") (class "Default")
      (node (ref "5V_1") (pin "P$2") (pinfunction "GND_P$2") (pintype "bidirectional"))
      (node (ref "U$1") (pin "P$27") (pinfunction "P_GND_P$27") (pintype "bidirectional"))
      (node (ref "U$2") (pin "P$5") (pinfunction "NI1_P$5") (pintype "bidirectional"))
    )
    (net (code "12") (name "/L") (class "Default")
      (node (ref "K2") (pin "1") (pinfunction "DS1_1") (pintype "passive"))
      (node (ref "K4") (pin "P1") (pinfunction "P_P1") (pintype "passive"))
      (node (ref "K4") (pin "P2") (pinfunction "P_P2") (pintype "passive"))
      (node (ref "K6") (pin "1") (pinfunction "1_1") (pintype "passive"))
      (node (ref "K6") (pin "O3") (pinfunction "O_O3") (pintype "passive"))
      (node (ref "L") (pin "P$2") (pinfunction "P$11_P$2") (pintype "bidirectional"))
      (node (ref "L10") (pin "P$2") (pinfunction "P$11_P$2") (pintype "bidirectional"))
      (node (ref "L5") (pin "P$2") (pinfunction "P$11_P$2") (pintype "bidirectional"))
      (node (ref "L6") (pin "P$2") (pinfunction "P$11_P$2") (pintype "bidirectional"))
      (node (ref "L7") (pin "P$2") (pinfunction "P$11_P$2") (pintype "bidirectional"))
      (node (ref "L8") (pin "P$2") (pinfunction "P$11_P$2") (pintype "bidirectional"))
      (node (ref "L9") (pin "P$2") (pinfunction "P$11_P$2") (pintype "bidirectional"))
      (node (ref "PC_ON") (pin "1") (pinfunction "1_1") (pintype "passive"))
    )
    (net (code "13") (name "/L1") (class "Default")
      (node (ref "12V_1") (pin "P$3") (pinfunction "L_P$3") (pintype "bidirectional"))
      (node (ref "5V_1") (pin "P$3") (pinfunction "L_P$3") (pintype "bidirectional"))
      (node (ref "5V_M1") (pin "P$3") (pinfunction "L_P$3") (pintype "bidirectional"))
      (node (ref "A_STECKDOSE_PC") (pin "P$2") (pinfunction "L_P$2") (pintype "bidirectional"))
      (node (ref "L1") (pin "P$2") (pinfunction "P$11_P$2") (pintype "bidirectional"))
      (node (ref "L2") (pin "P$2") (pinfunction "P$11_P$2") (pintype "bidirectional"))
      (node (ref "L3") (pin "P$2") (pinfunction "P$11_P$2") (pintype "bidirectional"))
      (node (ref "L4") (pin "P$2") (pinfunction "P$11_P$2") (pintype "bidirectional"))
      (node (ref "PC_ON") (pin "3") (pinfunction "3_3") (pintype "passive"))
    )
    (net (code "14") (name "/L2") (class "Default")
      (node (ref "36V_M") (pin "P$3") (pinfunction "L_P$3") (pintype "bidirectional"))
      (node (ref "A_STECKDOSE_VAC") (pin "P$2") (pinfunction "L_P$2") (pintype "bidirectional"))
      (node (ref "K4") (pin "O1") (pinfunction "O_O1") (pintype "passive"))
      (node (ref "K4") (pin "S2") (pinfunction "S_S2") (pintype "passive"))
      (node (ref "VFD") (pin "P$2") (pinfunction "L_P$2") (pintype "bidirectional"))
    )
    (net (code "15") (name "/L5") (class "Default")
      (node (ref "A_STECKDOSE_VPUMP") (pin "P$2") (pinfunction "L_P$2") (pintype "bidirectional"))
      (node (ref "K6") (pin "P3") (pinfunction "P_P3") (pintype "passive"))
    )
    (net (code "16") (name "/LASER_PWM") (class "Default")
      (node (ref "U$1") (pin "P$17") (pinfunction "17_P$17") (pintype "bidirectional"))
      (node (ref "U$12") (pin "1") (pinfunction "G_1") (pintype "passive"))
    )
    (net (code "17") (name "/N") (class "Default")
      (node (ref "12V_1") (pin "P$4") (pinfunction "N_P$4") (pintype "bidirectional"))
      (node (ref "36V_M") (pin "P$4") (pinfunction "N_P$4") (pintype "bidirectional"))
      (node (ref "5V_1") (pin "P$4") (pinfunction "N_P$4") (pintype "bidirectional"))
      (node (ref "5V_M1") (pin "P$4") (pinfunction "N_P$4") (pintype "bidirectional"))
      (node (ref "A_STECKDOSE_PC") (pin "P$3") (pinfunction "N_P$3") (pintype "bidirectional"))
      (node (ref "A_STECKDOSE_VAC") (pin "P$3") (pinfunction "N_P$3") (pintype "bidirectional"))
      (node (ref "A_STECKDOSE_VPUMP") (pin "P$3") (pinfunction "N_P$3") (pintype "bidirectional"))
      (node (ref "K4") (pin "1") (pinfunction "1_1") (pintype "passive"))
      (node (ref "K5") (pin "1") (pinfunction "DS1_1") (pintype "passive"))
      (node (ref "L18") (pin "P$2") (pinfunction "P$11_P$2") (pintype "bidirectional"))
      (node (ref "L19") (pin "P$1") (pinfunction "P$1_P$1") (pintype "bidirectional"))
      (node (ref "L19") (pin "P$2") (pinfunction "P$11_P$2") (pintype "bidirectional"))
      (node (ref "L20") (pin "P$2") (pinfunction "P$11_P$2") (pintype "bidirectional"))
      (node (ref "L21") (pin "P$2") (pinfunction "P$11_P$2") (pintype "bidirectional"))
      (node (ref "L23") (pin "P$2") (pinfunction "P$11_P$2") (pintype "bidirectional"))
      (node (ref "L24") (pin "P$2") (pinfunction "P$11_P$2") (pintype "bidirectional"))
      (node (ref "L25") (pin "P$1") (pinfunction "P$1_P$1") (pintype "bidirectional"))
      (node (ref "L25") (pin "P$2") (pinfunction "P$11_P$2") (pintype "bidirectional"))
      (node (ref "L26") (pin "P$1") (pinfunction "P$1_P$1") (pintype "bidirectional"))
      (node (ref "L26") (pin "P$2") (pinfunction "P$11_P$2") (pintype "bidirectional"))
      (node (ref "VFD") (pin "P$3") (pinfunction "N_P$3") (pintype "bidirectional"))
    )
    (net (code "18") (name "/N$41") (class "Default")
      (node (ref "FAN") (pin "P$1") (pinfunction "GND_P$1") (pintype "bidirectional"))
      (node (ref "JP5") (pin "2") (pinfunction "2_2") (pintype "passive"))
      (node (ref "LED") (pin "P$1") (pinfunction "GND_P$1") (pintype "bidirectional"))
      (node (ref "PUMP") (pin "P$1") (pinfunction "GND_P$1") (pintype "bidirectional"))
    )
    (net (code "19") (name "/N$42") (class "Default")
      (node (ref "FAN") (pin "P$2") (pinfunction "VCC_P$2") (pintype "bidirectional"))
      (node (ref "JP5") (pin "1") (pinfunction "1_1") (pintype "passive"))
      (node (ref "LED") (pin "P$2") (pinfunction "VCC_P$2") (pintype "bidirectional"))
      (node (ref "PUMP") (pin "P$2") (pinfunction "VCC_P$2") (pintype "bidirectional"))
    )
    (net (code "20") (name "/PC_OUT_14") (class "Default")
      (node (ref "K5") (pin "3") (pinfunction "K_3") (pintype "passive"))
      (node (ref "U$1") (pin "P$14") (pinfunction "14_P$14") (pintype "bidirectional"))
    )
    (net (code "21") (name "/PROBE") (class "Default")
      (node (ref "U$1") (pin "P$13") (pinfunction "13_P$13") (pintype "bidirectional"))
    )
    (net (code "22") (name "/RS485N") (class "Default")
      (node (ref "U$2") (pin "P$8") (pinfunction "P3_P$8") (pintype "bidirectional"))
    )
    (net (code "23") (name "/RS485P") (class "Default")
      (node (ref "U$2") (pin "P$4") (pinfunction "N3_P$4") (pintype "bidirectional"))
    )
    (net (code "24") (name "/X--{slash}HOME") (class "Default")
      (node (ref "SV1") (pin "6") (pinfunction "6_6") (pintype "passive"))
      (node (ref "SV2") (pin "6") (pinfunction "6_6") (pintype "passive"))
      (node (ref "U$1") (pin "P$10") (pinfunction "10_P$10") (pintype "bidirectional"))
      (node (ref "X--/HOME") (pin "3") (pinfunction "3_3") (pintype "passive"))
    )
    (net (code "25") (name "/X_DIR") (class "Default")
      (node (ref "U$1") (pin "P$4") (pinfunction "4_P$4") (pintype "bidirectional"))
      (node (ref "X") (pin "P$6") (pinfunction "DIR-_P$6") (pintype "bidirectional"))
    )
    (net (code "26") (name "/X_PUL") (class "Default")
      (node (ref "U$1") (pin "P$5") (pinfunction "5_P$5") (pintype "bidirectional"))
      (node (ref "X") (pin "P$11") (pinfunction "PUL-_P$11") (pintype "bidirectional"))
    )
    (net (code "27") (name "/Y--{slash}HOME") (class "Default")
      (node (ref "SV1") (pin "5") (pinfunction "5_5") (pintype "passive"))
      (node (ref "SV2") (pin "5") (pinfunction "5_5") (pintype "passive"))
      (node (ref "U$1") (pin "P$11") (pinfunction "11_P$11") (pintype "bidirectional"))
      (node (ref "Y--/HOME") (pin "3") (pinfunction "3_3") (pintype "passive"))
    )
    (net (code "28") (name "/Y_DIR") (class "Default")
      (node (ref "U$1") (pin "P$2") (pinfunction "2_P$2") (pintype "bidirectional"))
      (node (ref "Y") (pin "P$6") (pinfunction "DIR-_P$6") (pintype "bidirectional"))
    )
    (net (code "29") (name "/Y_PUL") (class "Default")
      (node (ref "U$1") (pin "P$3") (pinfunction "3_P$3") (pintype "bidirectional"))
      (node (ref "Y") (pin "P$11") (pinfunction "PUL-_P$11") (pintype "bidirectional"))
    )
    (net (code "30") (name "/Z++{slash}HOME") (class "Default")
      (node (ref "SV1") (pin "4") (pinfunction "4_4") (pintype "passive"))
      (node (ref "SV2") (pin "4") (pinfunction "4_4") (pintype "passive"))
      (node (ref "U$1") (pin "P$12") (pinfunction "12_P$12") (pintype "bidirectional"))
      (node (ref "Z--") (pin "3") (pinfunction "3_3") (pintype "passive"))
    )
    (net (code "31") (name "/Z_DIR") (class "Default")
      (node (ref "U$1") (pin "P$6") (pinfunction "6_P$6") (pintype "bidirectional"))
      (node (ref "Z") (pin "P$6") (pinfunction "DIR-_P$6") (pintype "bidirectional"))
    )
    (net (code "32") (name "/Z_PUL") (class "Default")
      (node (ref "U$1") (pin "P$7") (pinfunction "7_P$7") (pintype "bidirectional"))
      (node (ref "Z") (pin "P$11") (pinfunction "PUL-_P$11") (pintype "bidirectional"))
    )
    (net (code "33") (name "Net-(12V_PC-PadP$1)") (class "Default")
      (node (ref "12V_PC") (pin "P$1") (pinfunction "P$1_P$1") (pintype "bidirectional"))
      (node (ref "12V_PC1") (pin "P$1") (pinfunction "P$1_P$1") (pintype "bidirectional"))
      (node (ref "12V_PC2") (pin "P$1") (pinfunction "P$1_P$1") (pintype "bidirectional"))
      (node (ref "12V_PC3") (pin "P$1") (pinfunction "P$1_P$1") (pintype "bidirectional"))
    )
    (net (code "34") (name "Net-(36V-PadP$1)") (class "Default")
      (node (ref "36V") (pin "P$1") (pinfunction "P$1_P$1") (pintype "bidirectional"))
      (node (ref "36V1") (pin "P$1") (pinfunction "P$1_P$1") (pintype "bidirectional"))
      (node (ref "36V2") (pin "P$1") (pinfunction "P$1_P$1") (pintype "bidirectional"))
      (node (ref "36V3") (pin "P$1") (pinfunction "P$1_P$1") (pintype "bidirectional"))
    )
    (net (code "35") (name "Net-(FRAME-GND)") (class "Default")
      (node (ref "FRAME") (pin "P$1") (pinfunction "GND_P$1") (pintype "bidirectional"))
      (node (ref "JP4") (pin "2") (pinfunction "2_2") (pintype "passive"))
    )
    (net (code "36") (name "Net-(K2-DS2)") (class "Default")
      (node (ref "K2") (pin "2") (pinfunction "DS2_2") (pintype "passive"))
      (node (ref "K4") (pin "2") (pinfunction "2_2") (pintype "passive"))
    )
    (net (code "37") (name "Net-(K5-DS2)") (class "Default")
      (node (ref "K5") (pin "2") (pinfunction "DS2_2") (pintype "passive"))
      (node (ref "K6") (pin "2") (pinfunction "2_2") (pintype "passive"))
    )
    (net (code "38") (name "Net-(L1-PadP$1)") (class "Default")
      (node (ref "L1") (pin "P$1") (pinfunction "P$1_P$1") (pintype "bidirectional"))
      (node (ref "L2") (pin "P$1") (pinfunction "P$1_P$1") (pintype "bidirectional"))
      (node (ref "L3") (pin "P$1") (pinfunction "P$1_P$1") (pintype "bidirectional"))
      (node (ref "L4") (pin "P$1") (pinfunction "P$1_P$1") (pintype "bidirectional"))
    )
    (net (code "39") (name "Net-(LASER-GND)") (class "Default")
      (node (ref "JP1") (pin "2") (pinfunction "2_2") (pintype "passive"))
      (node (ref "LASER") (pin "P$1") (pinfunction "GND_P$1") (pintype "bidirectional"))
    )
    (net (code "40") (name "Net-(LASER-VCC)") (class "Default")
      (node (ref "JP1") (pin "1") (pinfunction "1_1") (pintype "passive"))
      (node (ref "LASER") (pin "P$2") (pinfunction "VCC_P$2") (pintype "bidirectional"))
    )
    (net (code "41") (name "Net-(SV3-Pad1)") (class "Default")
      (node (ref "SV3") (pin "1") (pinfunction "1_1") (pintype "passive"))
      (node (ref "U$3") (pin "P$4") (pinfunction "P$4_P$4") (pintype "bidirectional"))
    )
    (net (code "42") (name "Net-(SV3-Pad2)") (class "Default")
      (node (ref "SV3") (pin "2") (pinfunction "2_2") (pintype "passive"))
      (node (ref "U$3") (pin "P$3") (pinfunction "P$3_P$3") (pintype "bidirectional"))
    )
    (net (code "43") (name "Net-(SV3-Pad3)") (class "Default")
      (node (ref "SV3") (pin "3") (pinfunction "3_3") (pintype "passive"))
      (node (ref "U$3") (pin "P$2") (pinfunction "P$2_P$2") (pintype "bidirectional"))
    )
    (net (code "44") (name "Net-(SV3-Pad4)") (class "Default")
      (node (ref "SV3") (pin "4") (pinfunction "4_4") (pintype "passive"))
      (node (ref "U$3") (pin "P$1") (pinfunction "P$1_P$1") (pintype "bidirectional"))
    )
    (net (code "45") (name "Net-(SV7-Pad1)") (class "Default")
      (node (ref "SV7") (pin "1") (pinfunction "1_1") (pintype "passive"))
      (node (ref "U$7") (pin "P$4") (pinfunction "P$4_P$4") (pintype "bidirectional"))
    )
    (net (code "46") (name "Net-(SV7-Pad2)") (class "Default")
      (node (ref "SV7") (pin "2") (pinfunction "2_2") (pintype "passive"))
      (node (ref "U$7") (pin "P$3") (pinfunction "P$3_P$3") (pintype "bidirectional"))
    )
    (net (code "47") (name "Net-(SV7-Pad3)") (class "Default")
      (node (ref "SV7") (pin "3") (pinfunction "3_3") (pintype "passive"))
      (node (ref "U$7") (pin "P$2") (pinfunction "P$2_P$2") (pintype "bidirectional"))
    )
    (net (code "48") (name "Net-(SV7-Pad4)") (class "Default")
      (node (ref "SV7") (pin "4") (pinfunction "4_4") (pintype "passive"))
      (node (ref "U$7") (pin "P$1") (pinfunction "P$1_P$1") (pintype "bidirectional"))
    )
    (net (code "49") (name "Net-(SV8-Pad1)") (class "Default")
      (node (ref "SV8") (pin "1") (pinfunction "1_1") (pintype "passive"))
      (node (ref "U$8") (pin "P$4") (pinfunction "P$4_P$4") (pintype "bidirectional"))
    )
    (net (code "50") (name "Net-(SV8-Pad2)") (class "Default")
      (node (ref "SV8") (pin "2") (pinfunction "2_2") (pintype "passive"))
      (node (ref "U$8") (pin "P$3") (pinfunction "P$3_P$3") (pintype "bidirectional"))
    )
    (net (code "51") (name "Net-(SV8-Pad3)") (class "Default")
      (node (ref "SV8") (pin "3") (pinfunction "3_3") (pintype "passive"))
      (node (ref "U$8") (pin "P$2") (pinfunction "P$2_P$2") (pintype "bidirectional"))
    )
    (net (code "52") (name "Net-(SV8-Pad4)") (class "Default")
      (node (ref "SV8") (pin "4") (pinfunction "4_4") (pintype "passive"))
      (node (ref "U$8") (pin "P$1") (pinfunction "P$1_P$1") (pintype "bidirectional"))
    )
    (net (code "53") (name "Net-(U$1-02_PC)") (class "Default")
      (node (ref "U$1") (pin "P$32") (pinfunction "02_PC_P$32") (pintype "bidirectional"))
      (node (ref "U$4") (pin "P$39") (pinfunction "P$39_P$39") (pintype "bidirectional"))
    )
    (net (code "54") (name "Net-(U$1-03_PC)") (class "Default")
      (node (ref "U$1") (pin "P$33") (pinfunction "03_PC_P$33") (pintype "bidirectional"))
      (node (ref "U$4") (pin "P$48") (pinfunction "P$48_P$48") (pintype "bidirectional"))
    )
    (net (code "55") (name "Net-(U$1-04_PC)") (class "Default")
      (node (ref "U$1") (pin "P$34") (pinfunction "04_PC_P$34") (pintype "bidirectional"))
      (node (ref "U$4") (pin "P$38") (pinfunction "P$38_P$38") (pintype "bidirectional"))
    )
    (net (code "56") (name "Net-(U$1-05_PC)") (class "Default")
      (node (ref "U$1") (pin "P$35") (pinfunction "05_PC_P$35") (pintype "bidirectional"))
      (node (ref "U$4") (pin "P$46") (pinfunction "P$46_P$46") (pintype "bidirectional"))
    )
    (net (code "57") (name "Net-(U$1-06_PC)") (class "Default")
      (node (ref "U$1") (pin "P$36") (pinfunction "06_PC_P$36") (pintype "bidirectional"))
      (node (ref "U$4") (pin "P$40") (pinfunction "P$40_P$40") (pintype "bidirectional"))
    )
    (net (code "58") (name "Net-(U$1-07_PC)") (class "Default")
      (node (ref "U$1") (pin "P$37") (pinfunction "07_PC_P$37") (pintype "bidirectional"))
      (node (ref "U$4") (pin "P$49") (pinfunction "P$49_P$49") (pintype "bidirectional"))
    )
    (net (code "59") (name "Net-(U$1-10_PC)") (class "Default")
      (node (ref "U$1") (pin "P$40") (pinfunction "10_PC_P$40") (pintype "bidirectional"))
      (node (ref "U$4") (pin "P$41") (pinfunction "P$41_P$41") (pintype "bidirectional"))
    )
    (net (code "60") (name "Net-(U$1-11_PC)") (class "Default")
      (node (ref "U$1") (pin "P$41") (pinfunction "11_PC_P$41") (pintype "bidirectional"))
      (node (ref "U$4") (pin "P$35") (pinfunction "P$35_P$35") (pintype "bidirectional"))
    )
    (net (code "61") (name "Net-(U$1-12_PC)") (class "Default")
      (node (ref "U$1") (pin "P$42") (pinfunction "12_PC_P$42") (pintype "bidirectional"))
      (node (ref "U$4") (pin "P$50") (pinfunction "P$50_P$50") (pintype "bidirectional"))
    )
    (net (code "62") (name "Net-(U$1-13_PC)") (class "Default")
      (node (ref "U$1") (pin "P$43") (pinfunction "13_PC_P$43") (pintype "bidirectional"))
      (node (ref "U$4") (pin "P$44") (pinfunction "P$44_P$44") (pintype "bidirectional"))
    )
    (net (code "63") (name "Net-(U$1-15_PC)") (class "Default")
      (node (ref "U$1") (pin "P$45") (pinfunction "15_PC_P$45") (pintype "bidirectional"))
      (node (ref "U$4") (pin "P$36") (pinfunction "P$36_P$36") (pintype "bidirectional"))
    )
    (net (code "64") (name "Net-(U$1-17_PC)") (class "Default")
      (node (ref "U$1") (pin "P$47") (pinfunction "17_PC_P$47") (pintype "bidirectional"))
      (node (ref "U$4") (pin "P$22") (pinfunction "P$22_P$22") (pintype "bidirectional"))
    )
    (net (code "65") (name "Net-(U$10-PadP$1)") (class "Default")
      (node (ref "U$10") (pin "P$1") (pinfunction "P$1_P$1") (pintype "bidirectional"))
      (node (ref "U$11") (pin "P$1") (pinfunction "P$1_P$1") (pintype "bidirectional"))
      (node (ref "U$5") (pin "P$1") (pinfunction "P$1_P$1") (pintype "bidirectional"))
      (node (ref "U$6") (pin "P$1") (pinfunction "P$1_P$1") (pintype "bidirectional"))
      (node (ref "U$9") (pin "P$1") (pinfunction "P$1_P$1") (pintype "bidirectional"))
    )
    (net (code "66") (name "Net-(U$12-D)") (class "Default")
      (node (ref "JP2") (pin "2") (pinfunction "2_2") (pintype "passive"))
      (node (ref "U$12") (pin "3") (pinfunction "D_3") (pintype "passive"))
    )
    (net (code "67") (name "Net-(U$13-1X)") (class "Default")
      (node (ref "U$13") (pin "P$1") (pinfunction "1X_P$1") (pintype "bidirectional"))
      (node (ref "U$4") (pin "P$3") (pinfunction "P$3_P$3") (pintype "bidirectional"))
    )
    (net (code "68") (name "Net-(U$13-10X)") (class "Default")
      (node (ref "U$13") (pin "P$2") (pinfunction "10X_P$2") (pintype "bidirectional"))
      (node (ref "U$4") (pin "P$4") (pinfunction "P$4_P$4") (pintype "bidirectional"))
    )
    (net (code "69") (name "Net-(U$13-100X)") (class "Default")
      (node (ref "U$13") (pin "P$3") (pinfunction "100X_P$3") (pintype "bidirectional"))
      (node (ref "U$4") (pin "P$5") (pinfunction "P$5_P$5") (pintype "bidirectional"))
    )
    (net (code "70") (name "Net-(U$13-A)") (class "Default")
      (node (ref "U$13") (pin "P$4") (pinfunction "A_P$4") (pintype "bidirectional"))
      (node (ref "U$4") (pin "P$1") (pinfunction "P$1_P$1") (pintype "bidirectional"))
    )
    (net (code "71") (name "Net-(U$13-B)") (class "Default")
      (node (ref "U$13") (pin "P$5") (pinfunction "B_P$5") (pintype "bidirectional"))
      (node (ref "U$4") (pin "P$2") (pinfunction "P$2_P$2") (pintype "bidirectional"))
    )
    (net (code "72") (name "Net-(U$13-C)") (class "Default")
      (node (ref "U$13") (pin "P$6") (pinfunction "C_P$6") (pintype "bidirectional"))
      (node (ref "U$13") (pin "P$7") (pinfunction "COM_P$7") (pintype "bidirectional"))
      (node (ref "U$13") (pin "P$9") (pinfunction "GND_P$9") (pintype "bidirectional"))
      (node (ref "U$4") (pin "P$57") (pinfunction "GND_P$57") (pintype "bidirectional"))
    )
    (net (code "73") (name "Net-(U$13-E-STOP)") (class "Default")
      (node (ref "R1") (pin "1") (pinfunction "1_1") (pintype "passive"))
      (node (ref "U$13") (pin "P$8") (pinfunction "E-STOP_P$8") (pintype "bidirectional"))
      (node (ref "U$4") (pin "P$52") (pinfunction "P$52_P$52") (pintype "bidirectional"))
    )
    (net (code "74") (name "Net-(U$13-VCC)") (class "Default")
      (node (ref "R1") (pin "2") (pinfunction "2_2") (pintype "passive"))
      (node (ref "U$13") (pin "P$10") (pinfunction "VCC_P$10") (pintype "bidirectional"))
      (node (ref "U$4") (pin "P$58") (pinfunction "VCC_P$58") (pintype "bidirectional"))
    )
    (net (code "75") (name "Net-(U$13-X)") (class "Default")
      (node (ref "U$13") (pin "P$11") (pinfunction "X_P$11") (pintype "bidirectional"))
      (node (ref "U$4") (pin "P$6") (pinfunction "P$6_P$6") (pintype "bidirectional"))
    )
    (net (code "76") (name "Net-(U$13-Y)") (class "Default")
      (node (ref "U$13") (pin "P$12") (pinfunction "Y_P$12") (pintype "bidirectional"))
      (node (ref "U$4") (pin "P$7") (pinfunction "P$7_P$7") (pintype "bidirectional"))
    )
    (net (code "77") (name "Net-(U$13-Z)") (class "Default")
      (node (ref "U$13") (pin "P$13") (pinfunction "Z_P$13") (pintype "bidirectional"))
      (node (ref "U$4") (pin "P$9") (pinfunction "P$9_P$9") (pintype "bidirectional"))
    )
    (net (code "78") (name "Net-(X++-Pad1)") (class "Default")
      (node (ref "X++") (pin "1") (pinfunction "1_1") (pintype "passive"))
      (node (ref "Y++") (pin "1") (pinfunction "1_1") (pintype "passive"))
    )
    (net (code "79") (name "Net-(X-A+)") (class "Default")
      (node (ref "SV4") (pin "4") (pinfunction "4_4") (pintype "passive"))
      (node (ref "X") (pin "P$1") (pinfunction "A+_P$1") (pintype "bidirectional"))
    )
    (net (code "80") (name "Net-(X-A-)") (class "Default")
      (node (ref "SV4") (pin "3") (pinfunction "3_3") (pintype "passive"))
      (node (ref "X") (pin "P$2") (pinfunction "A-_P$2") (pintype "bidirectional"))
    )
    (net (code "81") (name "Net-(X-B+)") (class "Default")
      (node (ref "SV4") (pin "2") (pinfunction "2_2") (pintype "passive"))
      (node (ref "X") (pin "P$3") (pinfunction "B+_P$3") (pintype "bidirectional"))
    )
    (net (code "82") (name "Net-(X-B-)") (class "Default")
      (node (ref "SV4") (pin "1") (pinfunction "1_1") (pintype "passive"))
      (node (ref "X") (pin "P$4") (pinfunction "B-_P$4") (pintype "bidirectional"))
    )
    (net (code "83") (name "Net-(Y++-Pad3)") (class "Default")
      (node (ref "Y++") (pin "3") (pinfunction "3_3") (pintype "passive"))
      (node (ref "Z--/HOME") (pin "3") (pinfunction "3_3") (pintype "passive"))
    )
    (net (code "84") (name "Net-(Y-A+)") (class "Default")
      (node (ref "SV5") (pin "4") (pinfunction "4_4") (pintype "passive"))
      (node (ref "Y") (pin "P$1") (pinfunction "A+_P$1") (pintype "bidirectional"))
    )
    (net (code "85") (name "Net-(Y-A-)") (class "Default")
      (node (ref "SV5") (pin "3") (pinfunction "3_3") (pintype "passive"))
      (node (ref "Y") (pin "P$2") (pinfunction "A-_P$2") (pintype "bidirectional"))
    )
    (net (code "86") (name "Net-(Y-B+)") (class "Default")
      (node (ref "SV5") (pin "2") (pinfunction "2_2") (pintype "passive"))
      (node (ref "Y") (pin "P$3") (pinfunction "B+_P$3") (pintype "bidirectional"))
    )
    (net (code "87") (name "Net-(Y-B-)") (class "Default")
      (node (ref "SV5") (pin "1") (pinfunction "1_1") (pintype "passive"))
      (node (ref "Y") (pin "P$4") (pinfunction "B-_P$4") (pintype "bidirectional"))
    )
    (net (code "88") (name "Net-(Z-A+)") (class "Default")
      (node (ref "SV6") (pin "4") (pinfunction "4_4") (pintype "passive"))
      (node (ref "Z") (pin "P$1") (pinfunction "A+_P$1") (pintype "bidirectional"))
    )
    (net (code "89") (name "Net-(Z-A-)") (class "Default")
      (node (ref "SV6") (pin "3") (pinfunction "3_3") (pintype "passive"))
      (node (ref "Z") (pin "P$2") (pinfunction "A-_P$2") (pintype "bidirectional"))
    )
    (net (code "90") (name "Net-(Z-B+)") (class "Default")
      (node (ref "SV6") (pin "2") (pinfunction "2_2") (pintype "passive"))
      (node (ref "Z") (pin "P$3") (pinfunction "B+_P$3") (pintype "bidirectional"))
    )
    (net (code "91") (name "Net-(Z-B-)") (class "Default")
      (node (ref "SV6") (pin "1") (pinfunction "1_1") (pintype "passive"))
      (node (ref "Z") (pin "P$4") (pinfunction "B-_P$4") (pintype "bidirectional"))
    )
    (net (code "92") (name "unconnected-(5V_1-EAR-PadP$1)") (class "Default")
      (node (ref "5V_1") (pin "P$1") (pinfunction "EAR_P$1") (pintype "bidirectional"))
    )
    (net (code "93") (name "unconnected-(FRAME-VCC-PadP$2)") (class "Default")
      (node (ref "FRAME") (pin "P$2") (pinfunction "VCC_P$2") (pintype "bidirectional"))
    )
    (net (code "94") (name "unconnected-(GND_MACH-PadP$3)") (class "Default")
      (node (ref "GND_MACH") (pin "P$3") (pinfunction "P$3_P$3") (pintype "bidirectional"))
    )
    (net (code "95") (name "unconnected-(GND_MACH-PadP$4)") (class "Default")
      (node (ref "GND_MACH") (pin "P$4") (pinfunction "P$4_P$4") (pintype "bidirectional"))
    )
    (net (code "96") (name "unconnected-(GND_MACH-PadP$5)") (class "Default")
      (node (ref "GND_MACH") (pin "P$5") (pinfunction "P$5_P$5") (pintype "bidirectional"))
    )
    (net (code "97") (name "unconnected-(GND_MACH-PadP$6)") (class "Default")
      (node (ref "GND_MACH") (pin "P$6") (pinfunction "P$6_P$6") (pintype "bidirectional"))
    )
    (net (code "98") (name "unconnected-(GND_MACH-PadP$7)") (class "Default")
      (node (ref "GND_MACH") (pin "P$7") (pinfunction "P$7_P$7") (pintype "bidirectional"))
    )
    (net (code "99") (name "unconnected-(GND_MACH-PadP$8)") (class "Default")
      (node (ref "GND_MACH") (pin "P$8") (pinfunction "P$8_P$8") (pintype "bidirectional"))
    )
    (net (code "100") (name "unconnected-(GND_MACH-PadP$9)") (class "Default")
      (node (ref "GND_MACH") (pin "P$9") (pinfunction "P$9_P$9") (pintype "bidirectional"))
    )
    (net (code "101") (name "unconnected-(JP3-Pad1)") (class "Default")
      (node (ref "JP3") (pin "1") (pinfunction "1_1") (pintype "passive"))
    )
    (net (code "102") (name "unconnected-(JP4-Pad1)") (class "Default")
      (node (ref "JP4") (pin "1") (pinfunction "1_1") (pintype "passive"))
    )
    (net (code "103") (name "unconnected-(K4B-S-PadS1)") (class "Default")
      (node (ref "K4") (pin "S1") (pinfunction "S_S1") (pintype "passive"))
    )
    (net (code "104") (name "unconnected-(K4C-O-PadO2)") (class "Default")
      (node (ref "K4") (pin "O2") (pinfunction "O_O2") (pintype "passive"))
    )
    (net (code "105") (name "unconnected-(K4D-S-PadS3)") (class "Default")
      (node (ref "K4") (pin "S3") (pinfunction "S_S3") (pintype "passive"))
    )
    (net (code "106") (name "unconnected-(K6D-S-PadS3)") (class "Default")
      (node (ref "K6") (pin "S3") (pinfunction "S_S3") (pintype "passive"))
    )
    (net (code "107") (name "unconnected-(L-PadP$1)") (class "Default")
      (node (ref "L") (pin "P$1") (pinfunction "P$1_P$1") (pintype "bidirectional"))
    )
    (net (code "108") (name "unconnected-(L5-PadP$1)") (class "Default")
      (node (ref "L5") (pin "P$1") (pinfunction "P$1_P$1") (pintype "bidirectional"))
    )
    (net (code "109") (name "unconnected-(L6-PadP$1)") (class "Default")
      (node (ref "L6") (pin "P$1") (pinfunction "P$1_P$1") (pintype "bidirectional"))
    )
    (net (code "110") (name "unconnected-(L7-PadP$1)") (class "Default")
      (node (ref "L7") (pin "P$1") (pinfunction "P$1_P$1") (pintype "bidirectional"))
    )
    (net (code "111") (name "unconnected-(L8-PadP$1)") (class "Default")
      (node (ref "L8") (pin "P$1") (pinfunction "P$1_P$1") (pintype "bidirectional"))
    )
    (net (code "112") (name "unconnected-(L9-PadP$1)") (class "Default")
      (node (ref "L9") (pin "P$1") (pinfunction "P$1_P$1") (pintype "bidirectional"))
    )
    (net (code "113") (name "unconnected-(L10-PadP$1)") (class "Default")
      (node (ref "L10") (pin "P$1") (pinfunction "P$1_P$1") (pintype "bidirectional"))
    )
    (net (code "114") (name "unconnected-(L11-PadP$1)") (class "Default")
      (node (ref "L11") (pin "P$1") (pinfunction "P$1_P$1") (pintype "bidirectional"))
    )
    (net (code "115") (name "unconnected-(L16-P$11-PadP$2)") (class "Default")
      (node (ref "L16") (pin "P$2") (pinfunction "P$11_P$2") (pintype "bidirectional"))
    )
    (net (code "116") (name "unconnected-(L16-PadP$1)") (class "Default")
      (node (ref "L16") (pin "P$1") (pinfunction "P$1_P$1") (pintype "bidirectional"))
    )
    (net (code "117") (name "unconnected-(L17-PadP$1)") (class "Default")
      (node (ref "L17") (pin "P$1") (pinfunction "P$1_P$1") (pintype "bidirectional"))
    )
    (net (code "118") (name "unconnected-(L18-PadP$1)") (class "Default")
      (node (ref "L18") (pin "P$1") (pinfunction "P$1_P$1") (pintype "bidirectional"))
    )
    (net (code "119") (name "unconnected-(L20-PadP$1)") (class "Default")
      (node (ref "L20") (pin "P$1") (pinfunction "P$1_P$1") (pintype "bidirectional"))
    )
    (net (code "120") (name "unconnected-(L21-PadP$1)") (class "Default")
      (node (ref "L21") (pin "P$1") (pinfunction "P$1_P$1") (pintype "bidirectional"))
    )
    (net (code "121") (name "unconnected-(L23-PadP$1)") (class "Default")
      (node (ref "L23") (pin "P$1") (pinfunction "P$1_P$1") (pintype "bidirectional"))
    )
    (net (code "122") (name "unconnected-(L24-PadP$1)") (class "Default")
      (node (ref "L24") (pin "P$1") (pinfunction "P$1_P$1") (pintype "bidirectional"))
    )
    (net (code "123") (name "unconnected-(MACHINE-Pad2)") (class "Default")
      (node (ref "MACHINE") (pin "2") (pinfunction "2_2") (pintype "passive"))
    )
    (net (code "124") (name "unconnected-(MACHINE-Pad4)") (class "Default")
      (node (ref "MACHINE") (pin "4") (pinfunction "4_4") (pintype "passive"))
    )
    (net (code "125") (name "unconnected-(PC-EAR-PadP$1)") (class "Default")
      (node (ref "PC") (pin "P$1") (pinfunction "EAR_P$1") (pintype "bidirectional"))
    )
    (net (code "126") (name "unconnected-(PC-L-PadP$2)") (class "Default")
      (node (ref "PC") (pin "P$2") (pinfunction "L_P$2") (pintype "bidirectional"))
    )
    (net (code "127") (name "unconnected-(PC-N-PadP$3)") (class "Default")
      (node (ref "PC") (pin "P$3") (pinfunction "N_P$3") (pintype "bidirectional"))
    )
    (net (code "128") (name "unconnected-(PC_ON-Pad2)") (class "Default")
      (node (ref "PC_ON") (pin "2") (pinfunction "2_2") (pintype "passive"))
    )
    (net (code "129") (name "unconnected-(PC_ON-Pad4)") (class "Default")
      (node (ref "PC_ON") (pin "4") (pinfunction "4_4") (pintype "passive"))
    )
    (net (code "130") (name "unconnected-(SV1-Pad1)") (class "Default")
      (node (ref "SV1") (pin "1") (pinfunction "1_1") (pintype "passive"))
    )
    (net (code "131") (name "unconnected-(SV1-Pad2)") (class "Default")
      (node (ref "SV1") (pin "2") (pinfunction "2_2") (pintype "passive"))
    )
    (net (code "132") (name "unconnected-(SV1-Pad7)") (class "Default")
      (node (ref "SV1") (pin "7") (pinfunction "7_7") (pintype "passive"))
    )
    (net (code "133") (name "unconnected-(SV2-Pad1)") (class "Default")
      (node (ref "SV2") (pin "1") (pinfunction "1_1") (pintype "passive"))
    )
    (net (code "134") (name "unconnected-(SV2-Pad2)") (class "Default")
      (node (ref "SV2") (pin "2") (pinfunction "2_2") (pintype "passive"))
    )
    (net (code "135") (name "unconnected-(SV2-Pad7)") (class "Default")
      (node (ref "SV2") (pin "7") (pinfunction "7_7") (pintype "passive"))
    )
    (net (code "136") (name "unconnected-(U$1-1-PadP$1)") (class "Default")
      (node (ref "U$1") (pin "P$1") (pinfunction "1_P$1") (pintype "bidirectional"))
    )
    (net (code "137") (name "unconnected-(U$1-01_PC-PadP$31)") (class "Default")
      (node (ref "U$1") (pin "P$31") (pinfunction "01_PC_P$31") (pintype "bidirectional"))
    )
    (net (code "138") (name "unconnected-(U$1-8-PadP$8)") (class "Default")
      (node (ref "U$1") (pin "P$8") (pinfunction "8_P$8") (pintype "bidirectional"))
    )
    (net (code "139") (name "unconnected-(U$1-08_PC-PadP$38)") (class "Default")
      (node (ref "U$1") (pin "P$38") (pinfunction "08_PC_P$38") (pintype "bidirectional"))
    )
    (net (code "140") (name "unconnected-(U$1-9-PadP$9)") (class "Default")
      (node (ref "U$1") (pin "P$9") (pinfunction "9_P$9") (pintype "bidirectional"))
    )
    (net (code "141") (name "unconnected-(U$1-09_PC-PadP$39)") (class "Default")
      (node (ref "U$1") (pin "P$39") (pinfunction "09_PC_P$39") (pintype "bidirectional"))
    )
    (net (code "142") (name "unconnected-(U$1-14_PC-PadP$44)") (class "Default")
      (node (ref "U$1") (pin "P$44") (pinfunction "14_PC_P$44") (pintype "bidirectional"))
    )
    (net (code "143") (name "unconnected-(U$1-16-PadP$16)") (class "Default")
      (node (ref "U$1") (pin "P$16") (pinfunction "16_P$16") (pintype "bidirectional"))
    )
    (net (code "144") (name "unconnected-(U$1-16_PC-PadP$46)") (class "Default")
      (node (ref "U$1") (pin "P$46") (pinfunction "16_PC_P$46") (pintype "bidirectional"))
    )
    (net (code "145") (name "unconnected-(U$2-I1-PadP$1)") (class "Default")
      (node (ref "U$2") (pin "P$1") (pinfunction "I1_P$1") (pintype "bidirectional"))
    )
    (net (code "146") (name "unconnected-(U$2-N1-PadP$2)") (class "Default")
      (node (ref "U$2") (pin "P$2") (pinfunction "N1_P$2") (pintype "bidirectional"))
    )
    (net (code "147") (name "unconnected-(U$2-N2-PadP$3)") (class "Default")
      (node (ref "U$2") (pin "P$3") (pinfunction "N2_P$3") (pintype "bidirectional"))
    )
    (net (code "148") (name "unconnected-(U$2-P2-PadP$7)") (class "Default")
      (node (ref "U$2") (pin "P$7") (pinfunction "P2_P$7") (pintype "bidirectional"))
    )
    (net (code "149") (name "unconnected-(U$4-PadP$8)") (class "Default")
      (node (ref "U$4") (pin "P$8") (pinfunction "P$8_P$8") (pintype "bidirectional"))
    )
    (net (code "150") (name "unconnected-(U$4-PadP$10)") (class "Default")
      (node (ref "U$4") (pin "P$10") (pinfunction "P$10_P$10") (pintype "bidirectional"))
    )
    (net (code "151") (name "unconnected-(U$4-PadP$11)") (class "Default")
      (node (ref "U$4") (pin "P$11") (pinfunction "P$11_P$11") (pintype "bidirectional"))
    )
    (net (code "152") (name "unconnected-(U$4-PadP$12)") (class "Default")
      (node (ref "U$4") (pin "P$12") (pinfunction "P$12_P$12") (pintype "bidirectional"))
    )
    (net (code "153") (name "unconnected-(U$4-PadP$13)") (class "Default")
      (node (ref "U$4") (pin "P$13") (pinfunction "P$13_P$13") (pintype "bidirectional"))
    )
    (net (code "154") (name "unconnected-(U$4-PadP$14)") (class "Default")
      (node (ref "U$4") (pin "P$14") (pinfunction "P$14_P$14") (pintype "bidirectional"))
    )
    (net (code "155") (name "unconnected-(U$4-PadP$15)") (class "Default")
      (node (ref "U$4") (pin "P$15") (pinfunction "P$15_P$15") (pintype "bidirectional"))
    )
    (net (code "156") (name "unconnected-(U$4-PadP$16)") (class "Default")
      (node (ref "U$4") (pin "P$16") (pinfunction "P$16_P$16") (pintype "bidirectional"))
    )
    (net (code "157") (name "unconnected-(U$4-PadP$17)") (class "Default")
      (node (ref "U$4") (pin "P$17") (pinfunction "P$17_P$17") (pintype "bidirectional"))
    )
    (net (code "158") (name "unconnected-(U$4-PadP$18)") (class "Default")
      (node (ref "U$4") (pin "P$18") (pinfunction "P$18_P$18") (pintype "bidirectional"))
    )
    (net (code "159") (name "unconnected-(U$4-PadP$19)") (class "Default")
      (node (ref "U$4") (pin "P$19") (pinfunction "P$19_P$19") (pintype "bidirectional"))
    )
    (net (code "160") (name "unconnected-(U$4-PadP$20)") (class "Default")
      (node (ref "U$4") (pin "P$20") (pinfunction "P$20_P$20") (pintype "bidirectional"))
    )
    (net (code "161") (name "unconnected-(U$4-PadP$21)") (class "Default")
      (node (ref "U$4") (pin "P$21") (pinfunction "P$21_P$21") (pintype "bidirectional"))
    )
    (net (code "162") (name "unconnected-(U$4-PadP$23)") (class "Default")
      (node (ref "U$4") (pin "P$23") (pinfunction "P$23_P$23") (pintype "bidirectional"))
    )
    (net (code "163") (name "unconnected-(U$4-PadP$24)") (class "Default")
      (node (ref "U$4") (pin "P$24") (pinfunction "P$24_P$24") (pintype "bidirectional"))
    )
    (net (code "164") (name "unconnected-(U$4-PadP$25)") (class "Default")
      (node (ref "U$4") (pin "P$25") (pinfunction "P$25_P$25") (pintype "bidirectional"))
    )
    (net (code "165") (name "unconnected-(U$4-PadP$26)") (class "Default")
      (node (ref "U$4") (pin "P$26") (pinfunction "P$26_P$26") (pintype "bidirectional"))
    )
    (net (code "166") (name "unconnected-(U$4-PadP$27)") (class "Default")
      (node (ref "U$4") (pin "P$27") (pinfunction "P$27_P$27") (pintype "bidirectional"))
    )
    (net (code "167") (name "unconnected-(U$4-PadP$28)") (class "Default")
      (node (ref "U$4") (pin "P$28") (pinfunction "P$28_P$28") (pintype "bidirectional"))
    )
    (net (code "168") (name "unconnected-(U$4-PadP$29)") (class "Default")
      (node (ref "U$4") (pin "P$29") (pinfunction "P$29_P$29") (pintype "bidirectional"))
    )
    (net (code "169") (name "unconnected-(U$4-PadP$30)") (class "Default")
      (node (ref "U$4") (pin "P$30") (pinfunction "P$30_P$30") (pintype "bidirectional"))
    )
    (net (code "170") (name "unconnected-(U$4-PadP$31)") (class "Default")
      (node (ref "U$4") (pin "P$31") (pinfunction "P$31_P$31") (pintype "bidirectional"))
    )
    (net (code "171") (name "unconnected-(U$4-PadP$32)") (class "Default")
      (node (ref "U$4") (pin "P$32") (pinfunction "P$32_P$32") (pintype "bidirectional"))
    )
    (net (code "172") (name "unconnected-(U$4-PadP$33)") (class "Default")
      (node (ref "U$4") (pin "P$33") (pinfunction "P$33_P$33") (pintype "bidirectional"))
    )
    (net (code "173") (name "unconnected-(U$4-PadP$34)") (class "Default")
      (node (ref "U$4") (pin "P$34") (pinfunction "P$34_P$34") (pintype "bidirectional"))
    )
    (net (code "174") (name "unconnected-(U$4-PadP$37)") (class "Default")
      (node (ref "U$4") (pin "P$37") (pinfunction "P$37_P$37") (pintype "bidirectional"))
    )
    (net (code "175") (name "unconnected-(U$4-PadP$42)") (class "Default")
      (node (ref "U$4") (pin "P$42") (pinfunction "P$42_P$42") (pintype "bidirectional"))
    )
    (net (code "176") (name "unconnected-(U$4-PadP$43)") (class "Default")
      (node (ref "U$4") (pin "P$43") (pinfunction "P$43_P$43") (pintype "bidirectional"))
    )
    (net (code "177") (name "unconnected-(U$4-PadP$45)") (class "Default")
      (node (ref "U$4") (pin "P$45") (pinfunction "P$45_P$45") (pintype "bidirectional"))
    )
    (net (code "178") (name "unconnected-(U$4-PadP$47)") (class "Default")
      (node (ref "U$4") (pin "P$47") (pinfunction "P$47_P$47") (pintype "bidirectional"))
    )
    (net (code "179") (name "unconnected-(U$4-PadP$51)") (class "Default")
      (node (ref "U$4") (pin "P$51") (pinfunction "P$51_P$51") (pintype "bidirectional"))
    )
    (net (code "180") (name "unconnected-(U$4-PadP$53)") (class "Default")
      (node (ref "U$4") (pin "P$53") (pinfunction "P$53_P$53") (pintype "bidirectional"))
    )
    (net (code "181") (name "unconnected-(U$4-PadP$54)") (class "Default")
      (node (ref "U$4") (pin "P$54") (pinfunction "P$54_P$54") (pintype "bidirectional"))
    )
    (net (code "182") (name "unconnected-(U$4-PadP$55)") (class "Default")
      (node (ref "U$4") (pin "P$55") (pinfunction "P$55_P$55") (pintype "bidirectional"))
    )
    (net (code "183") (name "unconnected-(X++-Pad2)") (class "Default")
      (node (ref "X++") (pin "2") (pinfunction "2_2") (pintype "passive"))
    )
    (net (code "184") (name "unconnected-(X++-Pad4)") (class "Default")
      (node (ref "X++") (pin "4") (pinfunction "4_4") (pintype "passive"))
    )
    (net (code "185") (name "unconnected-(X--/HOME-Pad2)") (class "Default")
      (node (ref "X--/HOME") (pin "2") (pinfunction "2_2") (pintype "passive"))
    )
    (net (code "186") (name "unconnected-(X--/HOME-Pad4)") (class "Default")
      (node (ref "X--/HOME") (pin "4") (pinfunction "4_4") (pintype "passive"))
    )
    (net (code "187") (name "unconnected-(X-EN+-PadP$7)") (class "Default")
      (node (ref "X") (pin "P$7") (pinfunction "EN+_P$7") (pintype "bidirectional"))
    )
    (net (code "188") (name "unconnected-(Y++-Pad2)") (class "Default")
      (node (ref "Y++") (pin "2") (pinfunction "2_2") (pintype "passive"))
    )
    (net (code "189") (name "unconnected-(Y++-Pad4)") (class "Default")
      (node (ref "Y++") (pin "4") (pinfunction "4_4") (pintype "passive"))
    )
    (net (code "190") (name "unconnected-(Y--/HOME-Pad2)") (class "Default")
      (node (ref "Y--/HOME") (pin "2") (pinfunction "2_2") (pintype "passive"))
    )
    (net (code "191") (name "unconnected-(Y--/HOME-Pad4)") (class "Default")
      (node (ref "Y--/HOME") (pin "4") (pinfunction "4_4") (pintype "passive"))
    )
    (net (code "192") (name "unconnected-(Y-EN+-PadP$7)") (class "Default")
      (node (ref "Y") (pin "P$7") (pinfunction "EN+_P$7") (pintype "bidirectional"))
    )
    (net (code "193") (name "unconnected-(Z---Pad2)") (class "Default")
      (node (ref "Z--") (pin "2") (pinfunction "2_2") (pintype "passive"))
    )
    (net (code "194") (name "unconnected-(Z---Pad4)") (class "Default")
      (node (ref "Z--") (pin "4") (pinfunction "4_4") (pintype "passive"))
    )
    (net (code "195") (name "unconnected-(Z--/HOME-Pad2)") (class "Default")
      (node (ref "Z--/HOME") (pin "2") (pinfunction "2_2") (pintype "passive"))
    )
    (net (code "196") (name "unconnected-(Z--/HOME-Pad4)") (class "Default")
      (node (ref "Z--/HOME") (pin "4") (pinfunction "4_4") (pintype "passive"))
    )
    (net (code "197") (name "unconnected-(Z-EN+-PadP$7)") (class "Default")
      (node (ref "Z") (pin "P$7") (pinfunction "EN+_P$7") (pintype "bidirectional"))
    )
  )
)
